# AnalogSigCond1.net
KiCad netlist of a schematic drawn in Altium Designer
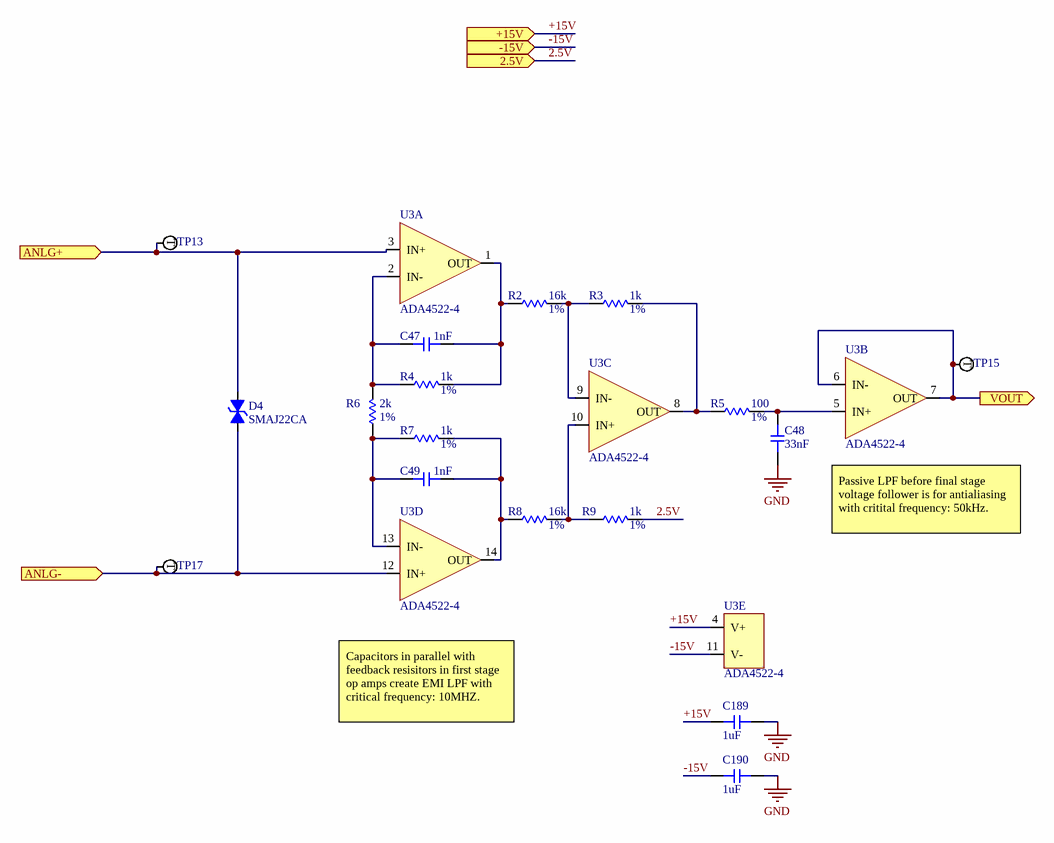
[diagram p0: AnalogSigCond1.SchDoc]

(export (version "E")
  (design (tool "Eeschema 10.0.6"))
  (components
    (comp (ref "C47")
      (value "Capacitor")
      (footprint "0603-CAP")
      (fields
        (field (name "MANUFACTURER") "KEMET")
        (field (name "MANUFACTURER PART NUMBER") "C0603C102J5RAC7867")
        (field (name "CAPACITANCE") "1nF")
        (field (name "TOLERANCE") "5%")
      )
      (libsource (lib "AMDC") (part "Capacitor"))
    )
    (comp (ref "C48")
      (value "Capacitor")
      (footprint "0603-CAP")
      (fields
        (field (name "MANUFACTURER") "Samsung")
        (field (name "MANUFACTURER PART NUMBER") "CL10B333KA8NNNC")
        (field (name "CAPACITANCE") "33nF")
        (field (name "TOLERANCE") "10%")
      )
      (libsource (lib "AMDC") (part "Capacitor"))
    )
    (comp (ref "C49")
      (value "Capacitor")
      (footprint "0603-CAP")
      (fields
        (field (name "MANUFACTURER") "KEMET")
        (field (name "MANUFACTURER PART NUMBER") "C0603C102J5RAC7867")
        (field (name "CAPACITANCE") "1nF")
        (field (name "TOLERANCE") "5%")
      )
      (libsource (lib "AMDC") (part "Capacitor"))
    )
    (comp (ref "C189")
      (value "1uF")
      (footprint "0603-CAP")
      (description "Capacitor")
      (fields
        (field (name "MANUFACTURER") "Samsung")
        (field (name "MANUFACTURER PART NUMBER") "CL10B105MO8NNWC")
      )
      (libsource (lib "AMDC") (part "Capacitor"))
    )
    (comp (ref "C190")
      (value "1uF")
      (footprint "0603-CAP")
      (description "Capacitor")
      (fields
        (field (name "MANUFACTURER") "Samsung")
        (field (name "MANUFACTURER PART NUMBER") "CL10B105MO8NNWC")
      )
      (libsource (lib "AMDC") (part "Capacitor"))
    )
    (comp (ref "D4")
      (value "TVS SMAJ22CA")
      (footprint "SMA")
      (description "TVS DIODE 22V 35.5V SMA")
      (fields (field (name "MANUFACTURER") "Bourns") (field (name "MANUFACTURER PART NUMBER") "SMAJ22CA"))
      (libsource (lib "AMDC") (part "TVS SMAJ22CA"))
    )
    (comp (ref "R2")
      (value "Resistor")
      (footprint "0603-RES")
      (fields
        (field (name "MANUFACTURER") "Panasonic")
        (field (name "MANUFACTURER PART NUMBER") "ERJ-3EKF1602V")
        (field (name "RESISTANCE") "16k")
        (field (name "TOLERANCE") "1%")
      )
      (libsource (lib "AMDC") (part "Resistor"))
    )
    (comp (ref "R3")
      (value "Resistor")
      (footprint "0603-RES")
      (fields
        (field (name "MANUFACTURER") "Panasonic")
        (field (name "MANUFACTURER PART NUMBER") "ERJ-3EKF1001V")
        (field (name "RESISTANCE") "1k")
        (field (name "TOLERANCE") "1%")
      )
      (libsource (lib "AMDC") (part "Resistor"))
    )
    (comp (ref "R4")
      (value "Resistor")
      (footprint "0603-RES")
      (fields
        (field (name "MANUFACTURER") "Panasonic")
        (field (name "MANUFACTURER PART NUMBER") "ERJ-3EKF1001V")
        (field (name "RESISTANCE") "1k")
        (field (name "TOLERANCE") "1%")
      )
      (libsource (lib "AMDC") (part "Resistor"))
    )
    (comp (ref "R5")
      (value "Resistor")
      (footprint "0603-RES")
      (fields
        (field (name "MANUFACTURER") "Yageo")
        (field (name "MANUFACTURER PART NUMBER") "AC0603FR-07100RL")
        (field (name "RESISTANCE") "100")
        (field (name "TOLERANCE") "1%")
      )
      (libsource (lib "AMDC") (part "Resistor"))
    )
    (comp (ref "R6")
      (value "Resistor")
      (footprint "0603-RES")
      (fields
        (field (name "MANUFACTURER") "Samsung")
        (field (name "MANUFACTURER PART NUMBER") "RC1608F202CS")
        (field (name "RESISTANCE") "2k")
        (field (name "TOLERANCE") "1%")
      )
      (libsource (lib "AMDC") (part "Resistor"))
    )
    (comp (ref "R7")
      (value "Resistor")
      (footprint "0603-RES")
      (fields
        (field (name "MANUFACTURER") "Panasonic")
        (field (name "MANUFACTURER PART NUMBER") "ERJ-3EKF1001V")
        (field (name "RESISTANCE") "1k")
        (field (name "TOLERANCE") "1%")
      )
      (libsource (lib "AMDC") (part "Resistor"))
    )
    (comp (ref "R8")
      (value "Resistor")
      (footprint "0603-RES")
      (fields
        (field (name "MANUFACTURER") "Panasonic")
        (field (name "MANUFACTURER PART NUMBER") "ERJ-3EKF1602V")
        (field (name "RESISTANCE") "16k")
        (field (name "TOLERANCE") "1%")
      )
      (libsource (lib "AMDC") (part "Resistor"))
    )
    (comp (ref "R9")
      (value "Resistor")
      (footprint "0603-RES")
      (fields
        (field (name "MANUFACTURER") "Panasonic")
        (field (name "MANUFACTURER PART NUMBER") "ERJ-3EKF1001V")
        (field (name "RESISTANCE") "1k")
        (field (name "TOLERANCE") "1%")
      )
      (libsource (lib "AMDC") (part "Resistor"))
    )
    (comp (ref "TP13") (value "Test Point") (footprint "RCU-0C") (libsource (lib "AMDC") (part "Test Point")))
    (comp (ref "TP15") (value "Test Point") (footprint "RCU-0C") (libsource (lib "AMDC") (part "Test Point")))
    (comp (ref "TP17") (value "Test Point") (footprint "RCU-0C") (libsource (lib "AMDC") (part "Test Point")))
    (comp (ref "U3")
      (value "ADA4522-4")
      (footprint "TSSOP-14")
      (fields
        (field (name "MANUFACTURER") "Analog Devices")
        (field (name "MANUFACTURER PART NUMBER") "ADA4522-4ARUZ-RL")
      )
      (libsource (lib "AMDC") (part "ADA4522-4"))
    )
  )
  (nets
    (net (code "1") (name "/+15V") (class "Default")
      (node (ref "C189") (pin "1") (pinfunction "1_1") (pintype "passive"))
      (node (ref "U3") (pin "4") (pinfunction "V+_4") (pintype "passive"))
    )
    (net (code "2") (name "/-15V") (class "Default")
      (node (ref "C190") (pin "1") (pinfunction "1_1") (pintype "passive"))
      (node (ref "U3") (pin "11") (pinfunction "V-_11") (pintype "passive"))
    )
    (net (code "3") (name "/2.5V") (class "Default")
      (node (ref "R9") (pin "2") (pinfunction "2_2") (pintype "passive"))
    )
    (net (code "4") (name "/ANLG+") (class "Default")
      (node (ref "D4") (pin "2") (pinfunction "2_2") (pintype "passive"))
      (node (ref "TP13") (pin "1") (pinfunction "1_1") (pintype "passive"))
      (node (ref "U3") (pin "3") (pinfunction "IN+_3") (pintype "passive"))
    )
    (net (code "5") (name "/ANLG-") (class "Default")
      (node (ref "D4") (pin "1") (pinfunction "1_1") (pintype "passive"))
      (node (ref "TP17") (pin "1") (pinfunction "1_1") (pintype "passive"))
      (node (ref "U3") (pin "12") (pinfunction "IN+_12") (pintype "passive"))
    )
    (net (code "6") (name "/VOUT") (class "Default")
      (node (ref "TP15") (pin "1") (pinfunction "1_1") (pintype "passive"))
      (node (ref "U3") (pin "6") (pinfunction "IN-_6") (pintype "passive"))
      (node (ref "U3") (pin "7") (pinfunction "OUT_7") (pintype "passive"))
    )
    (net (code "7") (name "GND") (class "Default")
      (node (ref "C189") (pin "2") (pinfunction "2_2") (pintype "passive"))
      (node (ref "C190") (pin "2") (pinfunction "2_2") (pintype "passive"))
      (node (ref "C48") (pin "1") (pinfunction "1_1") (pintype "passive"))
    )
    (net (code "8") (name "Net-(U3A-IN-)") (class "Default")
      (node (ref "C47") (pin "1") (pinfunction "1_1") (pintype "passive"))
      (node (ref "R4") (pin "1") (pinfunction "1_1") (pintype "passive"))
      (node (ref "R6") (pin "2") (pinfunction "2_2") (pintype "passive"))
      (node (ref "U3") (pin "2") (pinfunction "IN-_2") (pintype "passive"))
    )
    (net (code "9") (name "Net-(U3A-OUT)") (class "Default")
      (node (ref "C47") (pin "2") (pinfunction "2_2") (pintype "passive"))
      (node (ref "R2") (pin "1") (pinfunction "1_1") (pintype "passive"))
      (node (ref "R4") (pin "2") (pinfunction "2_2") (pintype "passive"))
      (node (ref "U3") (pin "1") (pinfunction "OUT_1") (pintype "passive"))
    )
    (net (code "10") (name "Net-(U3B-IN+)") (class "Default")
      (node (ref "C48") (pin "2") (pinfunction "2_2") (pintype "passive"))
      (node (ref "R5") (pin "2") (pinfunction "2_2") (pintype "passive"))
      (node (ref "U3") (pin "5") (pinfunction "IN+_5") (pintype "passive"))
    )
    (net (code "11") (name "Net-(U3C-IN+)") (class "Default")
      (node (ref "R8") (pin "2") (pinfunction "2_2") (pintype "passive"))
      (node (ref "R9") (pin "1") (pinfunction "1_1") (pintype "passive"))
      (node (ref "U3") (pin "10") (pinfunction "IN+_10") (pintype "passive"))
    )
    (net (code "12") (name "Net-(U3C-IN-)") (class "Default")
      (node (ref "R2") (pin "2") (pinfunction "2_2") (pintype "passive"))
      (node (ref "R3") (pin "1") (pinfunction "1_1") (pintype "passive"))
      (node (ref "U3") (pin "9") (pinfunction "IN-_9") (pintype "passive"))
    )
    (net (code "13") (name "Net-(U3C-OUT)") (class "Default")
      (node (ref "R3") (pin "2") (pinfunction "2_2") (pintype "passive"))
      (node (ref "R5") (pin "1") (pinfunction "1_1") (pintype "passive"))
      (node (ref "U3") (pin "8") (pinfunction "OUT_8") (pintype "passive"))
    )
    (net (code "14") (name "Net-(U3D-IN-)") (class "Default")
      (node (ref "C49") (pin "1") (pinfunction "1_1") (pintype "passive"))
      (node (ref "R6") (pin "1") (pinfunction "1_1") (pintype "passive"))
      (node (ref "R7") (pin "1") (pinfunction "1_1") (pintype "passive"))
      (node (ref "U3") (pin "13") (pinfunction "IN-_13") (pintype "passive"))
    )
    (net (code "15") (name "Net-(U3D-OUT)") (class "Default")
      (node (ref "C49") (pin "2") (pinfunction "2_2") (pintype "passive"))
      (node (ref "R7") (pin "2") (pinfunction "2_2") (pintype "passive"))
      (node (ref "R8") (pin "1") (pinfunction "1_1") (pintype "passive"))
      (node (ref "U3") (pin "14") (pinfunction "OUT_14") (pintype "passive"))
    )
  )
)
